# hbridge.net
KiCad netlist of a schematic drawn in EAGLE
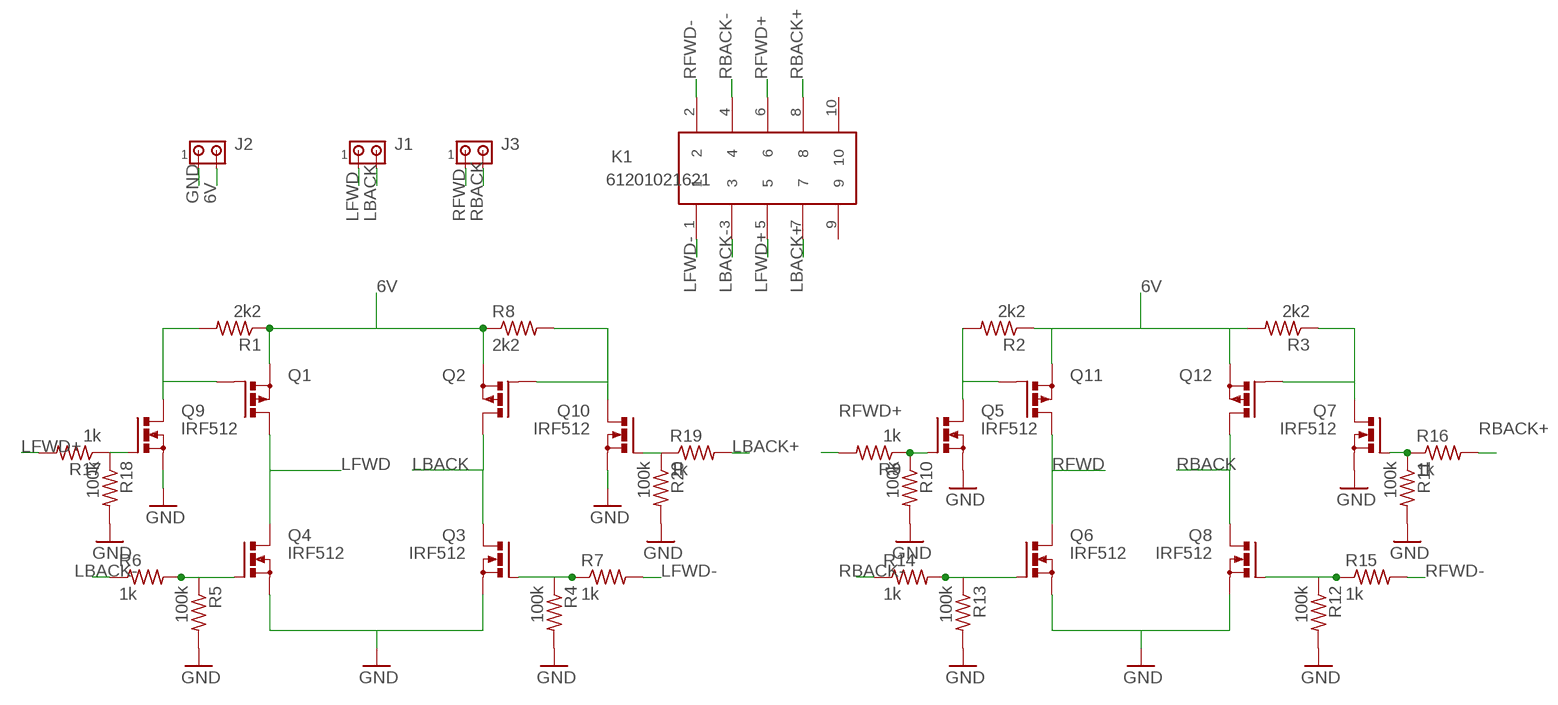
[diagram p0: schematic, sheet 1]

(export (version "E")
  (design (tool "Eeschema 10.0.6"))
  (components
    (comp (ref "J1")
      (value "MTA02-100")
      (footprint "eagle-import:10X02MTA")
      (libsource (lib "eagle-import") (part "MTA02-100"))
    )
    (comp (ref "J2")
      (value "MTA02-100")
      (footprint "eagle-import:10X02MTA")
      (libsource (lib "eagle-import") (part "MTA02-100"))
    )
    (comp (ref "J3")
      (value "MTA02-100")
      (footprint "eagle-import:10X02MTA")
      (libsource (lib "eagle-import") (part "MTA02-100"))
    )
    (comp (ref "K1")
      (value "61201021621")
      (footprint "eagle-import:61201021621")
      (libsource (lib "eagle-import") (part "61201021621"))
    )
    (comp (ref "Q1")
      (value "PMOSFET_PTO220BV")
      (footprint "eagle-import:TO220BV")
      (libsource (lib "eagle-import") (part "PMOSFET_PTO220BV"))
    )
    (comp (ref "Q2")
      (value "PMOSFET_PTO220BV")
      (footprint "eagle-import:TO220BV")
      (libsource (lib "eagle-import") (part "PMOSFET_PTO220BV"))
    )
    (comp (ref "Q3")
      (value "IRF512")
      (footprint "eagle-import:TO220BV")
      (libsource (lib "eagle-import") (part "IRF512"))
    )
    (comp (ref "Q4")
      (value "IRF512")
      (footprint "eagle-import:TO220BV")
      (libsource (lib "eagle-import") (part "IRF512"))
    )
    (comp (ref "Q5")
      (value "IRF512")
      (footprint "eagle-import:TO220BV")
      (libsource (lib "eagle-import") (part "IRF512"))
    )
    (comp (ref "Q6")
      (value "IRF512")
      (footprint "eagle-import:TO220BV")
      (libsource (lib "eagle-import") (part "IRF512"))
    )
    (comp (ref "Q7")
      (value "IRF512")
      (footprint "eagle-import:TO220BV")
      (libsource (lib "eagle-import") (part "IRF512"))
    )
    (comp (ref "Q8")
      (value "IRF512")
      (footprint "eagle-import:TO220BV")
      (libsource (lib "eagle-import") (part "IRF512"))
    )
    (comp (ref "Q9")
      (value "IRF512")
      (footprint "eagle-import:TO220BV")
      (libsource (lib "eagle-import") (part "IRF512"))
    )
    (comp (ref "Q10")
      (value "IRF512")
      (footprint "eagle-import:TO220BV")
      (libsource (lib "eagle-import") (part "IRF512"))
    )
    (comp (ref "Q11")
      (value "PMOSFET_PTO220BV")
      (footprint "eagle-import:TO220BV")
      (libsource (lib "eagle-import") (part "PMOSFET_PTO220BV"))
    )
    (comp (ref "Q12")
      (value "PMOSFET_PTO220BV")
      (footprint "eagle-import:TO220BV")
      (libsource (lib "eagle-import") (part "PMOSFET_PTO220BV"))
    )
    (comp (ref "R1")
      (value "2k2")
      (footprint "eagle-import:0204_7")
      (libsource (lib "eagle-import") (part "R-US_0204/7"))
    )
    (comp (ref "R2")
      (value "2k2")
      (footprint "eagle-import:0204_7")
      (libsource (lib "eagle-import") (part "R-US_0204/7"))
    )
    (comp (ref "R3")
      (value "2k2")
      (footprint "eagle-import:0204_7")
      (libsource (lib "eagle-import") (part "R-US_0204/7"))
    )
    (comp (ref "R4")
      (value "100k")
      (footprint "eagle-import:0204_7")
      (libsource (lib "eagle-import") (part "R-US_0204/7"))
    )
    (comp (ref "R5")
      (value "100k")
      (footprint "eagle-import:0204_7")
      (libsource (lib "eagle-import") (part "R-US_0204/7"))
    )
    (comp (ref "R6")
      (value "1k")
      (footprint "eagle-import:0204_7")
      (libsource (lib "eagle-import") (part "R-US_0204/7"))
    )
    (comp (ref "R7")
      (value "1k")
      (footprint "eagle-import:0204_7")
      (libsource (lib "eagle-import") (part "R-US_0204/7"))
    )
    (comp (ref "R8")
      (value "2k2")
      (footprint "eagle-import:0204_7")
      (libsource (lib "eagle-import") (part "R-US_0204/7"))
    )
    (comp (ref "R9")
      (value "1k")
      (footprint "eagle-import:0204_7")
      (libsource (lib "eagle-import") (part "R-US_0204/7"))
    )
    (comp (ref "R10")
      (value "100k")
      (footprint "eagle-import:0204_7")
      (libsource (lib "eagle-import") (part "R-US_0204/7"))
    )
    (comp (ref "R11")
      (value "100k")
      (footprint "eagle-import:0204_7")
      (libsource (lib "eagle-import") (part "R-US_0204/7"))
    )
    (comp (ref "R12")
      (value "100k")
      (footprint "eagle-import:0204_7")
      (libsource (lib "eagle-import") (part "R-US_0204/7"))
    )
    (comp (ref "R13")
      (value "100k")
      (footprint "eagle-import:0204_7")
      (libsource (lib "eagle-import") (part "R-US_0204/7"))
    )
    (comp (ref "R14")
      (value "1k")
      (footprint "eagle-import:0204_7")
      (libsource (lib "eagle-import") (part "R-US_0204/7"))
    )
    (comp (ref "R15")
      (value "1k")
      (footprint "eagle-import:0204_7")
      (libsource (lib "eagle-import") (part "R-US_0204/7"))
    )
    (comp (ref "R16")
      (value "1k")
      (footprint "eagle-import:0204_7")
      (libsource (lib "eagle-import") (part "R-US_0204/7"))
    )
    (comp (ref "R17")
      (value "1k")
      (footprint "eagle-import:0204_7")
      (libsource (lib "eagle-import") (part "R-US_0204/7"))
    )
    (comp (ref "R18")
      (value "100k")
      (footprint "eagle-import:0204_7")
      (libsource (lib "eagle-import") (part "R-US_0204/7"))
    )
    (comp (ref "R19")
      (value "1k")
      (footprint "eagle-import:0204_7")
      (libsource (lib "eagle-import") (part "R-US_0204/7"))
    )
    (comp (ref "R20")
      (value "100k")
      (footprint "eagle-import:0204_7")
      (libsource (lib "eagle-import") (part "R-US_0204/7"))
    )
  )
  (nets
    (net (code "1") (name "/6V") (class "Default")
      (node (ref "J2") (pin "2") (pinfunction "2_2") (pintype "passive"))
      (node (ref "Q1") (pin "S") (pinfunction "S_S") (pintype "passive"))
      (node (ref "Q11") (pin "S") (pinfunction "S_S") (pintype "passive"))
      (node (ref "Q12") (pin "S") (pinfunction "S_S") (pintype "passive"))
      (node (ref "Q2") (pin "S") (pinfunction "S_S") (pintype "passive"))
      (node (ref "R1") (pin "1") (pinfunction "1_1") (pintype "passive"))
      (node (ref "R2") (pin "1") (pinfunction "1_1") (pintype "passive"))
      (node (ref "R3") (pin "2") (pinfunction "2_2") (pintype "passive"))
      (node (ref "R8") (pin "1") (pinfunction "1_1") (pintype "passive"))
    )
    (net (code "2") (name "/LBACK") (class "Default")
      (node (ref "J1") (pin "2") (pinfunction "2_2") (pintype "passive"))
      (node (ref "Q2") (pin "D") (pinfunction "D_D") (pintype "passive"))
      (node (ref "Q3") (pin "D") (pinfunction "D_D") (pintype "passive"))
    )
    (net (code "3") (name "/LBACK+") (class "Default")
      (node (ref "K1") (pin "7") (pinfunction "7_7") (pintype "passive"))
      (node (ref "R19") (pin "2") (pinfunction "2_2") (pintype "passive"))
    )
    (net (code "4") (name "/LBACK-") (class "Default")
      (node (ref "K1") (pin "3") (pinfunction "3_3") (pintype "passive"))
      (node (ref "R6") (pin "1") (pinfunction "1_1") (pintype "passive"))
    )
    (net (code "5") (name "/LFWD") (class "Default")
      (node (ref "J1") (pin "1") (pinfunction "1_1") (pintype "passive"))
      (node (ref "Q1") (pin "D") (pinfunction "D_D") (pintype "passive"))
      (node (ref "Q4") (pin "D") (pinfunction "D_D") (pintype "passive"))
    )
    (net (code "6") (name "/LFWD+") (class "Default")
      (node (ref "K1") (pin "5") (pinfunction "5_5") (pintype "passive"))
      (node (ref "R17") (pin "2") (pinfunction "2_2") (pintype "passive"))
    )
    (net (code "7") (name "/LFWD-") (class "Default")
      (node (ref "K1") (pin "1") (pinfunction "1_1") (pintype "passive"))
      (node (ref "R7") (pin "2") (pinfunction "2_2") (pintype "passive"))
    )
    (net (code "8") (name "/RBACK") (class "Default")
      (node (ref "J3") (pin "2") (pinfunction "2_2") (pintype "passive"))
      (node (ref "Q12") (pin "D") (pinfunction "D_D") (pintype "passive"))
      (node (ref "Q8") (pin "D") (pinfunction "D_D") (pintype "passive"))
    )
    (net (code "9") (name "/RBACK+") (class "Default")
      (node (ref "K1") (pin "8") (pinfunction "8_8") (pintype "passive"))
      (node (ref "R16") (pin "2") (pinfunction "2_2") (pintype "passive"))
    )
    (net (code "10") (name "/RBACK-") (class "Default")
      (node (ref "K1") (pin "4") (pinfunction "4_4") (pintype "passive"))
      (node (ref "R14") (pin "1") (pinfunction "1_1") (pintype "passive"))
    )
    (net (code "11") (name "/RFWD") (class "Default")
      (node (ref "J3") (pin "1") (pinfunction "1_1") (pintype "passive"))
      (node (ref "Q11") (pin "D") (pinfunction "D_D") (pintype "passive"))
      (node (ref "Q6") (pin "D") (pinfunction "D_D") (pintype "passive"))
    )
    (net (code "12") (name "/RFWD+") (class "Default")
      (node (ref "K1") (pin "6") (pinfunction "6_6") (pintype "passive"))
      (node (ref "R9") (pin "2") (pinfunction "2_2") (pintype "passive"))
    )
    (net (code "13") (name "/RFWD-") (class "Default")
      (node (ref "K1") (pin "2") (pinfunction "2_2") (pintype "passive"))
      (node (ref "R15") (pin "2") (pinfunction "2_2") (pintype "passive"))
    )
    (net (code "14") (name "GND") (class "Default")
      (node (ref "J2") (pin "1") (pinfunction "1_1") (pintype "passive"))
      (node (ref "Q10") (pin "S") (pinfunction "S_S") (pintype "passive"))
      (node (ref "Q3") (pin "S") (pinfunction "S_S") (pintype "passive"))
      (node (ref "Q4") (pin "S") (pinfunction "S_S") (pintype "passive"))
      (node (ref "Q5") (pin "S") (pinfunction "S_S") (pintype "passive"))
      (node (ref "Q6") (pin "S") (pinfunction "S_S") (pintype "passive"))
      (node (ref "Q7") (pin "S") (pinfunction "S_S") (pintype "passive"))
      (node (ref "Q8") (pin "S") (pinfunction "S_S") (pintype "passive"))
      (node (ref "Q9") (pin "S") (pinfunction "S_S") (pintype "passive"))
      (node (ref "R10") (pin "2") (pinfunction "2_2") (pintype "passive"))
      (node (ref "R11") (pin "2") (pinfunction "2_2") (pintype "passive"))
      (node (ref "R12") (pin "2") (pinfunction "2_2") (pintype "passive"))
      (node (ref "R13") (pin "2") (pinfunction "2_2") (pintype "passive"))
      (node (ref "R18") (pin "2") (pinfunction "2_2") (pintype "passive"))
      (node (ref "R20") (pin "2") (pinfunction "2_2") (pintype "passive"))
      (node (ref "R4") (pin "2") (pinfunction "2_2") (pintype "passive"))
      (node (ref "R5") (pin "2") (pinfunction "2_2") (pintype "passive"))
    )
    (net (code "15") (name "Net-(Q1-PadG)") (class "Default")
      (node (ref "Q1") (pin "G") (pinfunction "G_G") (pintype "passive"))
      (node (ref "Q9") (pin "D") (pinfunction "D_D") (pintype "passive"))
      (node (ref "R1") (pin "2") (pinfunction "2_2") (pintype "passive"))
    )
    (net (code "16") (name "Net-(Q3-PadG)") (class "Default")
      (node (ref "Q3") (pin "G") (pinfunction "G_G") (pintype "passive"))
      (node (ref "R4") (pin "1") (pinfunction "1_1") (pintype "passive"))
      (node (ref "R7") (pin "1") (pinfunction "1_1") (pintype "passive"))
    )
    (net (code "17") (name "Net-(Q4-PadG)") (class "Default")
      (node (ref "Q4") (pin "G") (pinfunction "G_G") (pintype "passive"))
      (node (ref "R5") (pin "1") (pinfunction "1_1") (pintype "passive"))
      (node (ref "R6") (pin "2") (pinfunction "2_2") (pintype "passive"))
    )
    (net (code "18") (name "Net-(Q5-PadG)") (class "Default")
      (node (ref "Q5") (pin "G") (pinfunction "G_G") (pintype "passive"))
      (node (ref "R10") (pin "1") (pinfunction "1_1") (pintype "passive"))
      (node (ref "R9") (pin "1") (pinfunction "1_1") (pintype "passive"))
    )
    (net (code "19") (name "Net-(Q6-PadG)") (class "Default")
      (node (ref "Q6") (pin "G") (pinfunction "G_G") (pintype "passive"))
      (node (ref "R13") (pin "1") (pinfunction "1_1") (pintype "passive"))
      (node (ref "R14") (pin "2") (pinfunction "2_2") (pintype "passive"))
    )
    (net (code "20") (name "Net-(Q7-PadG)") (class "Default")
      (node (ref "Q7") (pin "G") (pinfunction "G_G") (pintype "passive"))
      (node (ref "R11") (pin "1") (pinfunction "1_1") (pintype "passive"))
      (node (ref "R16") (pin "1") (pinfunction "1_1") (pintype "passive"))
    )
    (net (code "21") (name "Net-(Q8-PadG)") (class "Default")
      (node (ref "Q8") (pin "G") (pinfunction "G_G") (pintype "passive"))
      (node (ref "R12") (pin "1") (pinfunction "1_1") (pintype "passive"))
      (node (ref "R15") (pin "1") (pinfunction "1_1") (pintype "passive"))
    )
    (net (code "22") (name "Net-(Q9-PadG)") (class "Default")
      (node (ref "Q9") (pin "G") (pinfunction "G_G") (pintype "passive"))
      (node (ref "R17") (pin "1") (pinfunction "1_1") (pintype "passive"))
      (node (ref "R18") (pin "1") (pinfunction "1_1") (pintype "passive"))
    )
    (net (code "23") (name "Net-(Q10-PadD)") (class "Default")
      (node (ref "Q10") (pin "D") (pinfunction "D_D") (pintype "passive"))
      (node (ref "Q2") (pin "G") (pinfunction "G_G") (pintype "passive"))
      (node (ref "R8") (pin "2") (pinfunction "2_2") (pintype "passive"))
    )
    (net (code "24") (name "Net-(Q10-PadG)") (class "Default")
      (node (ref "Q10") (pin "G") (pinfunction "G_G") (pintype "passive"))
      (node (ref "R19") (pin "1") (pinfunction "1_1") (pintype "passive"))
      (node (ref "R20") (pin "1") (pinfunction "1_1") (pintype "passive"))
    )
    (net (code "25") (name "Net-(Q11-PadG)") (class "Default")
      (node (ref "Q11") (pin "G") (pinfunction "G_G") (pintype "passive"))
      (node (ref "Q5") (pin "D") (pinfunction "D_D") (pintype "passive"))
      (node (ref "R2") (pin "2") (pinfunction "2_2") (pintype "passive"))
    )
    (net (code "26") (name "Net-(Q12-PadG)") (class "Default")
      (node (ref "Q12") (pin "G") (pinfunction "G_G") (pintype "passive"))
      (node (ref "Q7") (pin "D") (pinfunction "D_D") (pintype "passive"))
      (node (ref "R3") (pin "1") (pinfunction "1_1") (pintype "passive"))
    )
    (net (code "27") (name "unconnected-(K1-Pad9)") (class "Default")
      (node (ref "K1") (pin "9") (pinfunction "9_9") (pintype "passive"))
    )
    (net (code "28") (name "unconnected-(K1-Pad10)") (class "Default")
      (node (ref "K1") (pin "10") (pinfunction "10_10") (pintype "passive"))
    )
  )
)
